# Peripherals.net
KiCad netlist of a schematic drawn in Altium Designer
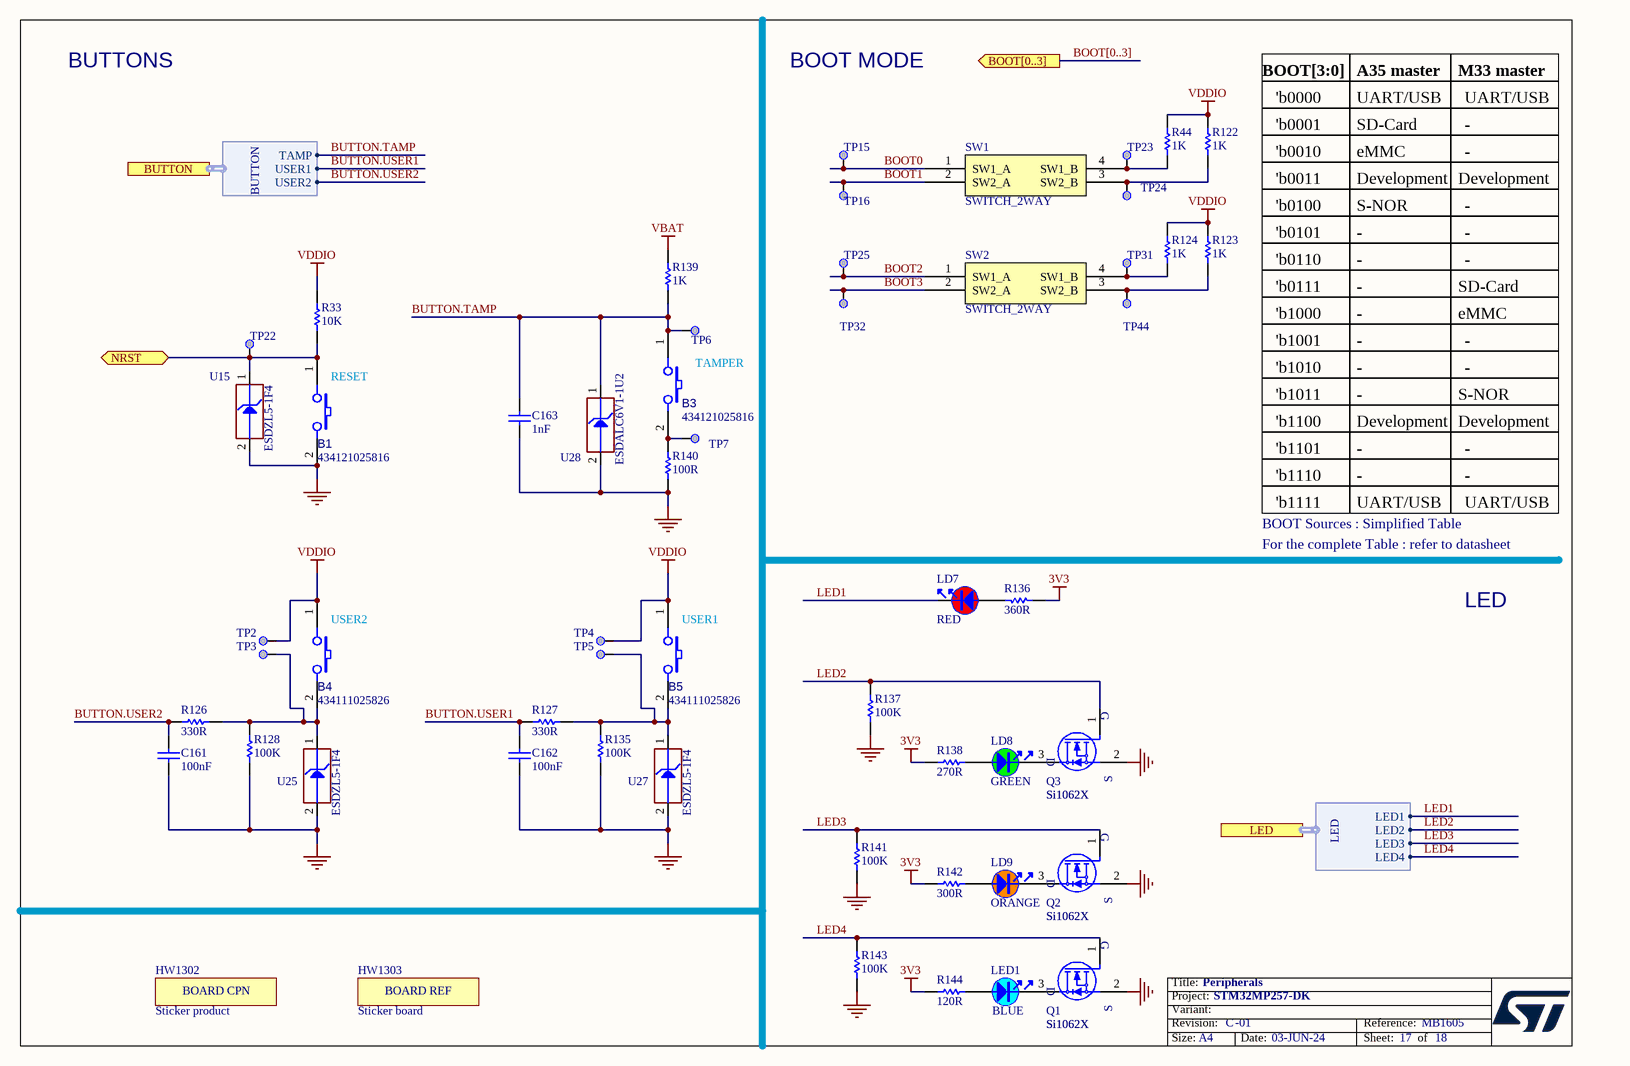
[diagram p0: Peripherals.SchDoc]

(export (version "E")
  (design (tool "Eeschema 10.0.6"))
  (components
    (comp (ref "B1")
      (value "434121025816")
      (footprint "SWI_WE_434121025816")
      (description "Switch tactile, SPST-NO, 50mA, 12V, 6x3.8mm")
      (fields
        (field (name "INTERNAL_PART_NUMBER") "MCD-03492")
        (field (name "MANUFACTURER") "WURTH ELEKTRONIC")
      )
      (libsource (lib "MCD_PARTS_database") (part "SW_PUSH_SMD_2P"))
    )
    (comp (ref "B3")
      (value "434121025816")
      (footprint "SWI_WE_434121025816")
      (description "Switch tactile, SPST-NO, 50mA, 12V, 6x3.8mm")
      (fields
        (field (name "INTERNAL_PART_NUMBER") "MCD-03492")
        (field (name "MANUFACTURER") "WURTH ELEKTRONIC")
      )
      (libsource (lib "MCD_PARTS_database") (part "SW_PUSH_SMD_2P"))
    )
    (comp (ref "B4")
      (value "434111025826")
      (footprint "SWI_WE_4341x10258x6")
      (description "Switch tactile, SPST-NO, 50mA, 12V, 6x3.8mm")
      (fields
        (field (name "INTERNAL_PART_NUMBER") "MCD-03491")
        (field (name "MANUFACTURER") "WURTH ELEKTRONIC")
      )
      (libsource (lib "MCD_PARTS_database") (part "SW_PUSH_SMD_2P"))
    )
    (comp (ref "B5")
      (value "434111025826")
      (footprint "SWI_WE_4341x10258x6")
      (description "Switch tactile, SPST-NO, 50mA, 12V, 6x3.8mm")
      (fields
        (field (name "INTERNAL_PART_NUMBER") "MCD-03491")
        (field (name "MANUFACTURER") "WURTH ELEKTRONIC")
      )
      (libsource (lib "MCD_PARTS_database") (part "SW_PUSH_SMD_2P"))
    )
    (comp (ref "C161")
      (value "100nF")
      (footprint "C0402")
      (description "Capacitor, MLCC, 100nF, 16V, X7R, +/-10%, 0402, T=0.5mm")
      (fields
        (field (name "INTERNAL_PART_NUMBER") "MCD-00006")
        (field (name "MANUFACTURER_PART_NUMBER") "CC0402KRX7R7BB104")
      )
      (libsource (lib "MCD_PARTS_database") (part "Capacitor"))
    )
    (comp (ref "C162")
      (value "100nF")
      (footprint "C0402")
      (description "Capacitor, MLCC, 100nF, 16V, X7R, +/-10%, 0402, T=0.5mm")
      (fields
        (field (name "INTERNAL_PART_NUMBER") "MCD-00006")
        (field (name "MANUFACTURER_PART_NUMBER") "CC0402KRX7R7BB104")
      )
      (libsource (lib "MCD_PARTS_database") (part "Capacitor"))
    )
    (comp (ref "C163")
      (value "1nF")
      (footprint "C0402")
      (description "Capacitor, MLCC, 1nF, 16V, X7R, +/-10%, 0402, T=0.5mm")
      (fields (field (name "INTERNAL_PART_NUMBER") "MCD-00198") (field (name "MANUFACTURER") "YAGEO"))
      (libsource (lib "MCD_PARTS_database") (part "Capacitor"))
    )
    (comp (ref "HW1302")
      (value "Sticker product")
      (footprint "STICKER_BOARD-CPN_25X5")
      (description "Sticker to mention board CPN code")
      (fields
        (field (name "INTERNAL_PART_NUMBER") "MCD-00547")
        (field (name "MANUFACTURER_PART_NUMBER") "n/a")
        (field (name "PROVIDED_BY") "SUBCO")
      )
      (libsource (lib "MCD_PARTS_database") (part "STICKER_BOARD_CPN"))
    )
    (comp (ref "HW1303")
      (value "Sticker board")
      (footprint "STICKER_BOARD-REF_25X5")
      (description "Sticker to mention board reference + serial number")
      (fields
        (field (name "INTERNAL_PART_NUMBER") "MCD-00235")
        (field (name "MANUFACTURER_PART_NUMBER") "n/a")
        (field (name "PROVIDED_BY") "SUBCO")
      )
      (libsource (lib "MCD_PARTS_database") (part "STICKER_BOARD_REF"))
    )
    (comp (ref "LD7")
      (value "RED")
      (footprint "LED_0603_VISHAY_VLMS1300-GS08_RED_1A2K_H0P8")
      (description "LED Red, 0603 SMD, 2V Forward Voltage")
      (fields
        (field (name "INTERNAL_PART_NUMBER") "MCD-00587")
        (field (name "MANUFACTURER_PART_NUMBER") "VLMS1300-GS08")
        (field (name "PROVIDED_BY") "SUBCO")
      )
      (libsource (lib "MCD_PARTS_database") (part "LED_red"))
    )
    (comp (ref "LD8")
      (value "GREEN")
      (footprint "LED_0603_OSRAM_LG-Q396-PS-35_GREEN_1A2K_H0P4")
      (description "LED Green, 0603 SMD, Forward Voltage Typ=2V, Max=2.5V")
      (fields
        (field (name "INTERNAL_PART_NUMBER") "MCD-00588")
        (field (name "MANUFACTURER_PART_NUMBER") "LG Q396-PS-35")
        (field (name "PROVIDED_BY") "SUBCO")
      )
      (libsource (lib "MCD_PARTS_database") (part "LED_green"))
    )
    (comp (ref "LD9")
      (value "ORANGE")
      (footprint "LED_0603_OSRAM_LO-Q976-PS-25_ORANGE_1A2K_H0P8")
      (description "LED Orange, 0603 SMD, Forward Voltage Min=1.6V, Max=2.4V")
      (fields
        (field (name "INTERNAL_PART_NUMBER") "MCD-00590")
        (field (name "MANUFACTURER_PART_NUMBER") "LO Q976-PS-25")
        (field (name "PROVIDED_BY") "SUBCO")
      )
      (libsource (lib "MCD_PARTS_database") (part "LED_orange"))
    )
    (comp (ref "LED1")
      (value "BLUE")
      (footprint "LED_0603_OSRAM_LB-Q39G-L2OO-35-1_BLUE_1A2K_H0P4")
      (description "LED Blue, 0603 SMD, Forward Voltage Min=2,8V, Max=3,8V")
      (fields
        (field (name "INTERNAL_PART_NUMBER") "MCD-00585")
        (field (name "MANUFACTURER_PART_NUMBER") "LB Q39G-L2OO-35-1")
        (field (name "PROVIDED_BY") "SUBCO")
      )
      (libsource (lib "MCD_PARTS_database") (part "LED_blue"))
    )
    (comp (ref "Q1")
      (value "Si1062X")
      (footprint "MOS_SC89-3L")
      (description "MOSFET N-CH 20V SC-89")
      (fields
        (field (name "INTERNAL_PART_NUMBER") "MCD-02221")
        (field (name "MANUFACTURER") "VISHAY")
        (field (name "MANUFACTURER_PART_NUMBER") "Si1062X")
      )
      (libsource (lib "MCD_PARTS_database") (part "MOSFET_N-CHANNEL"))
    )
    (comp (ref "Q2")
      (value "Si1062X")
      (footprint "MOS_SC89-3L")
      (description "MOSFET N-CH 20V SC-89")
      (fields
        (field (name "INTERNAL_PART_NUMBER") "MCD-02221")
        (field (name "MANUFACTURER") "VISHAY")
        (field (name "MANUFACTURER_PART_NUMBER") "Si1062X")
      )
      (libsource (lib "MCD_PARTS_database") (part "MOSFET_N-CHANNEL"))
    )
    (comp (ref "Q3")
      (value "Si1062X")
      (footprint "MOS_SC89-3L")
      (description "MOSFET N-CH 20V SC-89")
      (fields
        (field (name "INTERNAL_PART_NUMBER") "MCD-02221")
        (field (name "MANUFACTURER") "VISHAY")
        (field (name "MANUFACTURER_PART_NUMBER") "Si1062X")
      )
      (libsource (lib "MCD_PARTS_database") (part "MOSFET_N-CHANNEL"))
    )
    (comp (ref "R33")
      (value "10K")
      (footprint "R0402")
      (description "Resistor,10K,0402,1%,1/16W")
      (fields
        (field (name "INTERNAL_PART_NUMBER") "MCD-00053")
        (field (name "MANUFACTURER_PART_NUMBER") "RC0402FR-0710KL")
      )
      (libsource (lib "MCD_PARTS_database") (part "Resistor"))
    )
    (comp (ref "R44")
      (value "1K")
      (footprint "R0402")
      (description "Resistor,1K,0402,1%,1/16W")
      (fields (field (name "INTERNAL_PART_NUMBER") "MCD-00061") (field (name "MANUFACTURER") "YAGEO"))
      (libsource (lib "MCD_PARTS_database") (part "Resistor"))
    )
    (comp (ref "R122")
      (value "1K")
      (footprint "R0402")
      (description "Resistor,1K,0402,1%,1/16W")
      (fields (field (name "INTERNAL_PART_NUMBER") "MCD-00061") (field (name "MANUFACTURER") "YAGEO"))
      (libsource (lib "MCD_PARTS_database") (part "Resistor"))
    )
    (comp (ref "R123")
      (value "1K")
      (footprint "R0402")
      (description "Resistor,1K,0402,1%,1/16W")
      (fields (field (name "INTERNAL_PART_NUMBER") "MCD-00061") (field (name "MANUFACTURER") "YAGEO"))
      (libsource (lib "MCD_PARTS_database") (part "Resistor"))
    )
    (comp (ref "R124")
      (value "1K")
      (footprint "R0402")
      (description "Resistor,1K,0402,1%,1/16W")
      (fields (field (name "INTERNAL_PART_NUMBER") "MCD-00061") (field (name "MANUFACTURER") "YAGEO"))
      (libsource (lib "MCD_PARTS_database") (part "Resistor"))
    )
    (comp (ref "R126")
      (value "330R")
      (footprint "R0402")
      (description "Resistor,330R,0402,1%,1/16W")
      (fields
        (field (name "INTERNAL_PART_NUMBER") "MCD-00062")
        (field (name "MANUFACTURER_PART_NUMBER") "RC0402FR-07330RL")
      )
      (libsource (lib "MCD_PARTS_database") (part "Resistor"))
    )
    (comp (ref "R127")
      (value "330R")
      (footprint "R0402")
      (description "Resistor,330R,0402,1%,1/16W")
      (fields
        (field (name "INTERNAL_PART_NUMBER") "MCD-00062")
        (field (name "MANUFACTURER_PART_NUMBER") "RC0402FR-07330RL")
      )
      (libsource (lib "MCD_PARTS_database") (part "Resistor"))
    )
    (comp (ref "R128")
      (value "100K")
      (footprint "R0402")
      (description "Resistor,100K,0402,1%,1/16W")
      (fields
        (field (name "INTERNAL_PART_NUMBER") "MCD-00059")
        (field (name "MANUFACTURER_PART_NUMBER") "RC0402FR-07100KL")
      )
      (libsource (lib "MCD_PARTS_database") (part "Resistor"))
    )
    (comp (ref "R135")
      (value "100K")
      (footprint "R0402")
      (description "Resistor,100K,0402,1%,1/16W")
      (fields
        (field (name "INTERNAL_PART_NUMBER") "MCD-00059")
        (field (name "MANUFACTURER_PART_NUMBER") "RC0402FR-07100KL")
      )
      (libsource (lib "MCD_PARTS_database") (part "Resistor"))
    )
    (comp (ref "R136")
      (value "360R")
      (footprint "R0402")
      (description "Resistor,360R,0402,1%,1/16W")
      (fields
        (field (name "INTERNAL_PART_NUMBER") "MCD-00461")
        (field (name "MANUFACTURER_PART_NUMBER") "RC0402FR-07360RL")
        (field (name "PROVIDED_BY") "SUBCO")
      )
      (libsource (lib "MCD_PARTS_database") (part "Resistor"))
    )
    (comp (ref "R137")
      (value "100K")
      (footprint "R0402")
      (description "Resistor,100K,0402,1%,1/16W")
      (fields
        (field (name "INTERNAL_PART_NUMBER") "MCD-00059")
        (field (name "MANUFACTURER_PART_NUMBER") "RC0402FR-07100KL")
      )
      (libsource (lib "MCD_PARTS_database") (part "Resistor"))
    )
    (comp (ref "R138")
      (value "270R")
      (footprint "R0402")
      (description "Resistor,270R,0402,1%,1/16W")
      (fields
        (field (name "INTERNAL_PART_NUMBER") "MCD-00441")
        (field (name "MANUFACTURER_PART_NUMBER") "RC0402FR-07270RL")
        (field (name "PROVIDED_BY") "SUBCO")
      )
      (libsource (lib "MCD_PARTS_database") (part "Resistor"))
    )
    (comp (ref "R139")
      (value "1K")
      (footprint "R0402")
      (description "Resistor, 1K, 0402, +/-1%,1/16W")
      (fields
        (field (name "INTERNAL_PART_NUMBER") "MCD-00061")
        (field (name "MANUFACTURER_PART_NUMBER") "RC0402FR-071KL")
      )
      (libsource (lib "MCD_PARTS_database") (part "Resistor"))
    )
    (comp (ref "R140")
      (value "100R")
      (footprint "R0402")
      (description "Resistor, 100R, 0402, +/- 1%, 1/16W")
      (fields
        (field (name "INTERNAL_PART_NUMBER") "MCD-00067")
        (field (name "MANUFACTURER_PART_NUMBER") "RC0402FR-07100RL")
      )
      (libsource (lib "MCD_PARTS_database") (part "Resistor"))
    )
    (comp (ref "R141")
      (value "100K")
      (footprint "R0402")
      (description "Resistor,100K,0402,1%,1/16W")
      (fields
        (field (name "INTERNAL_PART_NUMBER") "MCD-00059")
        (field (name "MANUFACTURER_PART_NUMBER") "RC0402FR-07100KL")
      )
      (libsource (lib "MCD_PARTS_database") (part "Resistor"))
    )
    (comp (ref "R142")
      (value "300R")
      (footprint "R0402")
      (description "Resistor,300R,0402,1%,1/16W")
      (fields
        (field (name "INTERNAL_PART_NUMBER") "MCD-00449")
        (field (name "MANUFACTURER_PART_NUMBER") "RC0402FR-07300RL")
        (field (name "PROVIDED_BY") "SUBCO")
      )
      (libsource (lib "MCD_PARTS_database") (part "Resistor"))
    )
    (comp (ref "R143")
      (value "100K")
      (footprint "R0402")
      (description "Resistor,100K,0402,1%,1/16W")
      (fields
        (field (name "INTERNAL_PART_NUMBER") "MCD-00059")
        (field (name "MANUFACTURER_PART_NUMBER") "RC0402FR-07100KL")
      )
      (libsource (lib "MCD_PARTS_database") (part "Resistor"))
    )
    (comp (ref "R144")
      (value "120R")
      (footprint "R0402")
      (description "Resistor,120R,0402,1%,1/16W")
      (fields
        (field (name "INTERNAL_PART_NUMBER") "MCD-00194")
        (field (name "MANUFACTURER_PART_NUMBER") "RC0402FR-07120RL")
        (field (name "PROVIDED_BY") "SUBCO")
      )
      (libsource (lib "MCD_PARTS_database") (part "Resistor"))
    )
    (comp (ref "SW1")
      (value "SWITCH_2WAY")
      (footprint "SWI_C&K_SDA02H1SBD_2POS")
      (description "Dip Switch ,2Position ,Surface Mount Slide (Standard) ,2.54 pitch,25mA 24VDC")
      (fields (field (name "INTERNAL_PART_NUMBER") "MCD-00658") (field (name "MANUFACTURER") "C&K"))
      (libsource (lib "MCD_PARTS_database") (part "SWITCH_2WAY"))
    )
    (comp (ref "SW2")
      (value "SWITCH_2WAY")
      (footprint "SWI_C&K_SDA02H1SBD_2POS")
      (description "Dip Switch ,2Position ,Surface Mount Slide (Standard) ,2.54 pitch,25mA 24VDC")
      (fields (field (name "INTERNAL_PART_NUMBER") "MCD-00658") (field (name "MANUFACTURER") "C&K"))
      (libsource (lib "MCD_PARTS_database") (part "SWITCH_2WAY"))
    )
    (comp (ref "TP2")
      (value "Test Point")
      (footprint "TP_SMD_1MM")
      (description "Test Point 1mm")
      (fields
        (field (name "INTERNAL_PART_NUMBER") "MCD-00074")
        (field (name "MANUFACTURER_PART_NUMBER") "n/a")
      )
      (libsource (lib "MCD_PARTS_database") (part "Test Point"))
    )
    (comp (ref "TP3")
      (value "Test Point")
      (footprint "TP_SMD_1MM")
      (description "Test Point 1mm")
      (fields
        (field (name "INTERNAL_PART_NUMBER") "MCD-00074")
        (field (name "MANUFACTURER_PART_NUMBER") "n/a")
      )
      (libsource (lib "MCD_PARTS_database") (part "Test Point"))
    )
    (comp (ref "TP4")
      (value "Test Point")
      (footprint "TP_SMD_1MM")
      (description "Test Point 1mm")
      (fields
        (field (name "INTERNAL_PART_NUMBER") "MCD-00074")
        (field (name "MANUFACTURER_PART_NUMBER") "n/a")
      )
      (libsource (lib "MCD_PARTS_database") (part "Test Point"))
    )
    (comp (ref "TP5")
      (value "Test Point")
      (footprint "TP_SMD_1MM")
      (description "Test Point 1mm")
      (fields
        (field (name "INTERNAL_PART_NUMBER") "MCD-00074")
        (field (name "MANUFACTURER_PART_NUMBER") "n/a")
      )
      (libsource (lib "MCD_PARTS_database") (part "Test Point"))
    )
    (comp (ref "TP6")
      (value "Test Point")
      (footprint "TP_SMD_1MM")
      (description "Test Point 1mm")
      (fields
        (field (name "INTERNAL_PART_NUMBER") "MCD-00074")
        (field (name "MANUFACTURER_PART_NUMBER") "n/a")
      )
      (libsource (lib "") (part "Test Point_3"))
    )
    (comp (ref "TP7")
      (value "Test Point")
      (footprint "TP_SMD_1MM")
      (description "Test Point 1mm")
      (fields
        (field (name "INTERNAL_PART_NUMBER") "MCD-00074")
        (field (name "MANUFACTURER_PART_NUMBER") "n/a")
      )
      (libsource (lib "") (part "Test Point_3"))
    )
    (comp (ref "TP15")
      (value "Test Point")
      (footprint "TP_SMD_1MM")
      (description "Test Point 1mm")
      (fields
        (field (name "INTERNAL_PART_NUMBER") "MCD-00074")
        (field (name "MANUFACTURER_PART_NUMBER") "n/a")
      )
      (libsource (lib "") (part "Test Point_2"))
    )
    (comp (ref "TP16")
      (value "Test Point")
      (footprint "TP_SMD_1MM")
      (description "Test Point 1mm")
      (fields
        (field (name "INTERNAL_PART_NUMBER") "MCD-00074")
        (field (name "MANUFACTURER_PART_NUMBER") "n/a")
      )
      (libsource (lib "") (part "Test Point_1"))
    )
    (comp (ref "TP22")
      (value "Test Point")
      (footprint "TP_SMD_1MM")
      (description "Test Point 1mm")
      (fields
        (field (name "INTERNAL_PART_NUMBER") "MCD-00074")
        (field (name "MANUFACTURER_PART_NUMBER") "n/a")
      )
      (libsource (lib "") (part "Test Point_2"))
    )
    (comp (ref "TP23")
      (value "Test Point")
      (footprint "TP_SMD_1MM")
      (description "Test Point 1mm")
      (fields
        (field (name "INTERNAL_PART_NUMBER") "MCD-00074")
        (field (name "MANUFACTURER_PART_NUMBER") "n/a")
      )
      (libsource (lib "") (part "Test Point_2"))
    )
    (comp (ref "TP24")
      (value "Test Point")
      (footprint "TP_SMD_1MM")
      (description "Test Point 1mm")
      (fields
        (field (name "INTERNAL_PART_NUMBER") "MCD-00074")
        (field (name "MANUFACTURER_PART_NUMBER") "n/a")
      )
      (libsource (lib "") (part "Test Point_1"))
    )
    (comp (ref "TP25")
      (value "Test Point")
      (footprint "TP_SMD_1MM")
      (description "Test Point 1mm")
      (fields
        (field (name "INTERNAL_PART_NUMBER") "MCD-00074")
        (field (name "MANUFACTURER_PART_NUMBER") "n/a")
      )
      (libsource (lib "") (part "Test Point_2"))
    )
    (comp (ref "TP31")
      (value "Test Point")
      (footprint "TP_SMD_1MM")
      (description "Test Point 1mm")
      (fields
        (field (name "INTERNAL_PART_NUMBER") "MCD-00074")
        (field (name "MANUFACTURER_PART_NUMBER") "n/a")
      )
      (libsource (lib "") (part "Test Point_2"))
    )
    (comp (ref "TP32")
      (value "Test Point")
      (footprint "TP_SMD_1MM")
      (description "Test Point 1mm")
      (fields
        (field (name "INTERNAL_PART_NUMBER") "MCD-00074")
        (field (name "MANUFACTURER_PART_NUMBER") "n/a")
      )
      (libsource (lib "") (part "Test Point_1"))
    )
    (comp (ref "TP44")
      (value "Test Point")
      (footprint "TP_SMD_1MM")
      (description "Test Point 1mm")
      (fields
        (field (name "INTERNAL_PART_NUMBER") "MCD-00074")
        (field (name "MANUFACTURER_PART_NUMBER") "n/a")
      )
      (libsource (lib "") (part "Test Point_1"))
    )
    (comp (ref "U15")
      (value "ESDZL5-1F4")
      (footprint "ESD_ST0201")
      (description "ESD protection , 0201")
      (fields
        (field (name "INTERNAL_PART_NUMBER") "MCD-03501")
        (field (name "MANUFACTURER") "STMICROELECTRONICS")
      )
      (libsource (lib "MCD_PARTS_database") (part "ESD-TRANSIL"))
    )
    (comp (ref "U25")
      (value "ESDZL5-1F4")
      (footprint "ESD_ST0201")
      (description "ESD protection , 0201")
      (fields
        (field (name "INTERNAL_PART_NUMBER") "MCD-03501")
        (field (name "MANUFACTURER") "STMICROELECTRONICS")
      )
      (libsource (lib "MCD_PARTS_database") (part "ESD-TRANSIL"))
    )
    (comp (ref "U27")
      (value "ESDZL5-1F4")
      (footprint "ESD_ST0201")
      (description "ESD protection , 0201")
      (fields
        (field (name "INTERNAL_PART_NUMBER") "MCD-03501")
        (field (name "MANUFACTURER") "STMICROELECTRONICS")
      )
      (libsource (lib "MCD_PARTS_database") (part "ESD-TRANSIL"))
    )
    (comp (ref "U28")
      (value "ESDALC6V1-1U2")
      (footprint "ESD_ST0201")
      (description "ESD protection 6V1")
      (fields
        (field (name "INTERNAL_PART_NUMBER") "MCD-00170")
        (field (name "MANUFACTURER") "STMICROELECTRONICS")
      )
      (libsource (lib "MCD_PARTS_database") (part "ESD-TRANSIL"))
    )
  )
  (nets
    (net (code "3") (name "/BOOT0") (class "Default")
      (node (ref "SW1") (pin "1") (pinfunction "SW1_A_1") (pintype "passive"))
      (node (ref "TP15") (pin "1") (pinfunction "1_1") (pintype "passive"))
    )
    (net (code "4") (name "/BOOT1") (class "Default")
      (node (ref "SW1") (pin "2") (pinfunction "SW2_A_2") (pintype "passive"))
      (node (ref "TP16") (pin "1") (pinfunction "1_1") (pintype "passive"))
    )
    (net (code "5") (name "/BOOT2") (class "Default")
      (node (ref "SW2") (pin "1") (pinfunction "SW1_A_1") (pintype "passive"))
      (node (ref "TP25") (pin "1") (pinfunction "1_1") (pintype "passive"))
    )
    (net (code "6") (name "/BOOT3") (class "Default")
      (node (ref "SW2") (pin "2") (pinfunction "SW2_A_2") (pintype "passive"))
      (node (ref "TP32") (pin "1") (pinfunction "1_1") (pintype "passive"))
    )
    (net (code "8") (name "/BUTTON.TAMP") (class "Default")
      (node (ref "B3") (pin "1") (pinfunction "1_1") (pintype "passive"))
      (node (ref "C163") (pin "2") (pinfunction "2_2") (pintype "passive"))
      (node (ref "R139") (pin "1") (pinfunction "1_1") (pintype "passive"))
      (node (ref "TP6") (pin "1") (pinfunction "1_1") (pintype "passive"))
      (node (ref "U28") (pin "1") (pinfunction "IO1_1") (pintype "passive"))
    )
    (net (code "9") (name "/BUTTON.USER1") (class "Default")
      (node (ref "C162") (pin "2") (pinfunction "2_2") (pintype "passive"))
      (node (ref "R127") (pin "1") (pinfunction "1_1") (pintype "passive"))
    )
    (net (code "10") (name "/BUTTON.USER2") (class "Default")
      (node (ref "C161") (pin "2") (pinfunction "2_2") (pintype "passive"))
      (node (ref "R126") (pin "1") (pinfunction "1_1") (pintype "passive"))
    )
    (net (code "11") (name "/LED1") (class "Default") (node (ref "LD7") (pin "2") (pintype "passive")))
    (net (code "12") (name "/LED2") (class "Default")
      (node (ref "Q3") (pin "1") (pinfunction "G_1") (pintype "passive"))
      (node (ref "R137") (pin "2") (pinfunction "2_2") (pintype "passive"))
    )
    (net (code "13") (name "/LED3") (class "Default")
      (node (ref "Q2") (pin "1") (pinfunction "G_1") (pintype "passive"))
      (node (ref "R141") (pin "2") (pinfunction "2_2") (pintype "passive"))
    )
    (net (code "14") (name "/LED4") (class "Default")
      (node (ref "Q1") (pin "1") (pinfunction "G_1") (pintype "passive"))
      (node (ref "R143") (pin "2") (pinfunction "2_2") (pintype "passive"))
    )
    (net (code "15") (name "/NRST") (class "Default")
      (node (ref "B1") (pin "1") (pinfunction "1_1") (pintype "passive"))
      (node (ref "R33") (pin "1") (pinfunction "1_1") (pintype "passive"))
      (node (ref "TP22") (pin "1") (pinfunction "1_1") (pintype "passive"))
      (node (ref "U15") (pin "1") (pinfunction "IO1_1") (pintype "passive"))
    )
    (net (code "18") (name "3V3") (class "Default")
      (node (ref "R136") (pin "1") (pinfunction "1_1") (pintype "passive"))
      (node (ref "R138") (pin "2") (pinfunction "2_2") (pintype "passive"))
      (node (ref "R142") (pin "2") (pinfunction "2_2") (pintype "passive"))
      (node (ref "R144") (pin "1") (pinfunction "1_1") (pintype "passive"))
    )
    (net (code "19") (name "GND") (class "Default")
      (node (ref "B1") (pin "2") (pinfunction "2_2") (pintype "passive"))
      (node (ref "C161") (pin "1") (pinfunction "1_1") (pintype "passive"))
      (node (ref "C162") (pin "1") (pinfunction "1_1") (pintype "passive"))
      (node (ref "C163") (pin "1") (pinfunction "1_1") (pintype "passive"))
      (node (ref "Q1") (pin "2") (pinfunction "S_2") (pintype "passive"))
      (node (ref "Q2") (pin "2") (pinfunction "S_2") (pintype "passive"))
      (node (ref "Q3") (pin "2") (pinfunction "S_2") (pintype "passive"))
      (node (ref "R128") (pin "1") (pinfunction "1_1") (pintype "passive"))
      (node (ref "R135") (pin "1") (pinfunction "1_1") (pintype "passive"))
      (node (ref "R137") (pin "1") (pinfunction "1_1") (pintype "passive"))
      (node (ref "R140") (pin "2") (pinfunction "2_2") (pintype "passive"))
      (node (ref "R141") (pin "1") (pinfunction "1_1") (pintype "passive"))
      (node (ref "R143") (pin "1") (pinfunction "1_1") (pintype "passive"))
      (node (ref "U15") (pin "2") (pinfunction "GND_2") (pintype "passive"))
      (node (ref "U25") (pin "2") (pinfunction "GND_2") (pintype "passive"))
      (node (ref "U27") (pin "2") (pinfunction "GND_2") (pintype "passive"))
      (node (ref "U28") (pin "2") (pinfunction "GND_2") (pintype "passive"))
    )
    (net (code "20") (name "Net-(B3-Pad2)") (class "Default")
      (node (ref "B3") (pin "2") (pinfunction "2_2") (pintype "passive"))
      (node (ref "R140") (pin "1") (pinfunction "1_1") (pintype "passive"))
      (node (ref "TP7") (pin "1") (pinfunction "1_1") (pintype "passive"))
    )
    (net (code "21") (name "Net-(LD7-Pad1)") (class "Default")
      (node (ref "LD7") (pin "1") (pintype "passive"))
      (node (ref "R136") (pin "2") (pinfunction "2_2") (pintype "passive"))
    )
    (net (code "22") (name "Net-(LD8-Pad1)") (class "Default")
      (node (ref "LD8") (pin "1") (pintype "passive"))
      (node (ref "R138") (pin "1") (pinfunction "1_1") (pintype "passive"))
    )
    (net (code "23") (name "Net-(LD9-Pad1)") (class "Default")
      (node (ref "LD9") (pin "1") (pintype "passive"))
      (node (ref "R142") (pin "1") (pinfunction "1_1") (pintype "passive"))
    )
    (net (code "24") (name "Net-(LED1-Pad1)") (class "Default")
      (node (ref "LED1") (pin "1") (pintype "passive"))
      (node (ref "R144") (pin "2") (pinfunction "2_2") (pintype "passive"))
    )
    (net (code "25") (name "Net-(Q1-D)") (class "Default")
      (node (ref "LED1") (pin "2") (pintype "passive"))
      (node (ref "Q1") (pin "3") (pinfunction "D_3") (pintype "passive"))
    )
    (net (code "26") (name "Net-(Q2-D)") (class "Default")
      (node (ref "LD9") (pin "2") (pintype "passive"))
      (node (ref "Q2") (pin "3") (pinfunction "D_3") (pintype "passive"))
    )
    (net (code "27") (name "Net-(Q3-D)") (class "Default")
      (node (ref "LD8") (pin "2") (pintype "passive"))
      (node (ref "Q3") (pin "3") (pinfunction "D_3") (pintype "passive"))
    )
    (net (code "28") (name "Net-(SW1-SW1_B)") (class "Default")
      (node (ref "R44") (pin "1") (pinfunction "1_1") (pintype "passive"))
      (node (ref "SW1") (pin "4") (pinfunction "SW1_B_4") (pintype "passive"))
      (node (ref "TP23") (pin "1") (pinfunction "1_1") (pintype "passive"))
    )
    (net (code "29") (name "Net-(SW1-SW2_B)") (class "Default")
      (node (ref "R122") (pin "1") (pinfunction "1_1") (pintype "passive"))
      (node (ref "SW1") (pin "3") (pinfunction "SW2_B_3") (pintype "passive"))
      (node (ref "TP24") (pin "1") (pinfunction "1_1") (pintype "passive"))
    )
    (net (code "30") (name "Net-(SW2-SW1_B)") (class "Default")
      (node (ref "R124") (pin "1") (pinfunction "1_1") (pintype "passive"))
      (node (ref "SW2") (pin "4") (pinfunction "SW1_B_4") (pintype "passive"))
      (node (ref "TP31") (pin "1") (pinfunction "1_1") (pintype "passive"))
    )
    (net (code "31") (name "Net-(SW2-SW2_B)") (class "Default")
      (node (ref "R123") (pin "1") (pinfunction "1_1") (pintype "passive"))
      (node (ref "SW2") (pin "3") (pinfunction "SW2_B_3") (pintype "passive"))
      (node (ref "TP44") (pin "1") (pinfunction "1_1") (pintype "passive"))
    )
    (net (code "32") (name "Net-(U25-IO1)") (class "Default")
      (node (ref "B4") (pin "2") (pinfunction "2_2") (pintype "passive"))
      (node (ref "R126") (pin "2") (pinfunction "2_2") (pintype "passive"))
      (node (ref "R128") (pin "2") (pinfunction "2_2") (pintype "passive"))
      (node (ref "TP3") (pin "1") (pinfunction "1_1") (pintype "passive"))
      (node (ref "U25") (pin "1") (pinfunction "IO1_1") (pintype "passive"))
    )
    (net (code "33") (name "Net-(U27-IO1)") (class "Default")
      (node (ref "B5") (pin "2") (pinfunction "2_2") (pintype "passive"))
      (node (ref "R127") (pin "2") (pinfunction "2_2") (pintype "passive"))
      (node (ref "R135") (pin "2") (pinfunction "2_2") (pintype "passive"))
      (node (ref "TP5") (pin "1") (pinfunction "1_1") (pintype "passive"))
      (node (ref "U27") (pin "1") (pinfunction "IO1_1") (pintype "passive"))
    )
    (net (code "34") (name "VBAT") (class "Default")
      (node (ref "R139") (pin "2") (pinfunction "2_2") (pintype "passive"))
    )
    (net (code "35") (name "VDDIO") (class "Default")
      (node (ref "B4") (pin "1") (pinfunction "1_1") (pintype "passive"))
      (node (ref "B5") (pin "1") (pinfunction "1_1") (pintype "passive"))
      (node (ref "R122") (pin "2") (pinfunction "2_2") (pintype "passive"))
      (node (ref "R123") (pin "2") (pinfunction "2_2") (pintype "passive"))
      (node (ref "R124") (pin "2") (pinfunction "2_2") (pintype "passive"))
      (node (ref "R33") (pin "2") (pinfunction "2_2") (pintype "passive"))
      (node (ref "R44") (pin "2") (pinfunction "2_2") (pintype "passive"))
      (node (ref "TP2") (pin "1") (pinfunction "1_1") (pintype "passive"))
      (node (ref "TP4") (pin "1") (pinfunction "1_1") (pintype "passive"))
    )
  )
)
